# MCISO-S06-V00-HALL_DIFFB.net
KiCad netlist of a schematic drawn in Altium Designer
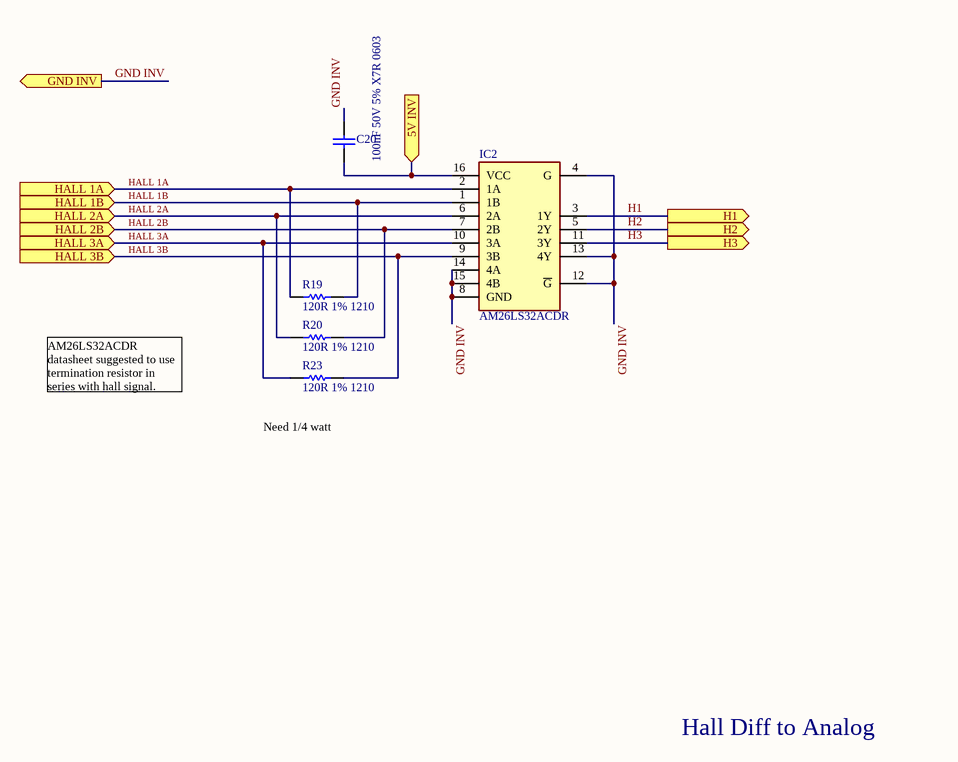
[diagram p0: MCISO-S06-V00-HALL_DIFFB.SchDoc]

(export (version "E")
  (design (tool "Eeschema 10.0.6"))
  (components
    (comp (ref "C20")
      (value "100nF 50V 5% X7R 0603")
      (footprint "Cap_Ceramic_0603")
      (description "Capacitor, Ceramic, SMD, 100nF, 50V, 5%, X7R, 0603")
      (libsource (lib "StandardCapacitors") (part "100nF 50V 5% X7R 0603"))
    )
    (comp (ref "IC2")
      (value "AM26LS32ACDR")
      (footprint "SamacSys:SOIC127P600X175-16N")
      (description "Integrated Circuit")
      (fields (field (name "MOUSER PART NUMBER") "595-AM26LS32ACDR"))
      (libsource (lib "QUTMS-MCISOLibrary") (part "AM26LS32ACDR"))
    )
    (comp (ref "R19")
      (value "120R 1% 1210")
      (footprint "Res_ThinFilm_1210")
      (description "Resistor, SMD, 120R, 0.25W, 1%, 1210")
      (libsource (lib "StandardResistors") (part "120R 1% 1210"))
    )
    (comp (ref "R20")
      (value "120R 1% 1210")
      (footprint "Res_ThinFilm_1210")
      (description "Resistor, SMD, 120R, 0.25W, 1%, 1210")
      (libsource (lib "StandardResistors") (part "120R 1% 1210"))
    )
    (comp (ref "R23")
      (value "120R 1% 1210")
      (footprint "Res_ThinFilm_1210")
      (description "Resistor, SMD, 120R, 0.25W, 1%, 1210")
      (libsource (lib "StandardResistors") (part "120R 1% 1210"))
    )
  )
  (nets
    (net (code "1") (name "/5V INV") (class "Default")
      (node (ref "C20") (pin "1") (pinfunction "1_1") (pintype "passive"))
      (node (ref "IC2") (pin "16") (pinfunction "VCC_16") (pintype "passive"))
    )
    (net (code "2") (name "/GND INV") (class "Default")
      (node (ref "C20") (pin "2") (pinfunction "2_2") (pintype "passive"))
      (node (ref "IC2") (pin "12") (pinfunction "~{G}_12") (pintype "passive"))
      (node (ref "IC2") (pin "13") (pinfunction "4Y_13") (pintype "passive"))
      (node (ref "IC2") (pin "14") (pinfunction "4A_14") (pintype "passive"))
      (node (ref "IC2") (pin "15") (pinfunction "4B_15") (pintype "passive"))
      (node (ref "IC2") (pin "4") (pinfunction "G_4") (pintype "passive"))
      (node (ref "IC2") (pin "8") (pinfunction "GND_8") (pintype "passive"))
    )
    (net (code "3") (name "/H1") (class "Default")
      (node (ref "IC2") (pin "3") (pinfunction "1Y_3") (pintype "passive"))
    )
    (net (code "4") (name "/H2") (class "Default")
      (node (ref "IC2") (pin "5") (pinfunction "2Y_5") (pintype "passive"))
    )
    (net (code "5") (name "/H3") (class "Default")
      (node (ref "IC2") (pin "11") (pinfunction "3Y_11") (pintype "passive"))
    )
    (net (code "6") (name "/HALL 1A") (class "Default")
      (node (ref "IC2") (pin "2") (pinfunction "1A_2") (pintype "passive"))
      (node (ref "R19") (pin "1") (pinfunction "1_1") (pintype "passive"))
    )
    (net (code "7") (name "/HALL 1B") (class "Default")
      (node (ref "IC2") (pin "1") (pinfunction "1B_1") (pintype "passive"))
      (node (ref "R19") (pin "2") (pinfunction "2_2") (pintype "passive"))
    )
    (net (code "8") (name "/HALL 2A") (class "Default")
      (node (ref "IC2") (pin "6") (pinfunction "2A_6") (pintype "passive"))
      (node (ref "R20") (pin "1") (pinfunction "1_1") (pintype "passive"))
    )
    (net (code "9") (name "/HALL 2B") (class "Default")
      (node (ref "IC2") (pin "7") (pinfunction "2B_7") (pintype "passive"))
      (node (ref "R20") (pin "2") (pinfunction "2_2") (pintype "passive"))
    )
    (net (code "10") (name "/HALL 3A") (class "Default")
      (node (ref "IC2") (pin "10") (pinfunction "3A_10") (pintype "passive"))
      (node (ref "R23") (pin "1") (pinfunction "1_1") (pintype "passive"))
    )
    (net (code "11") (name "/HALL 3B") (class "Default")
      (node (ref "IC2") (pin "9") (pinfunction "3B_9") (pintype "passive"))
      (node (ref "R23") (pin "2") (pinfunction "2_2") (pintype "passive"))
    )
  )
)
